# Sheet1.net
KiCad netlist of a schematic drawn in Altium Designer
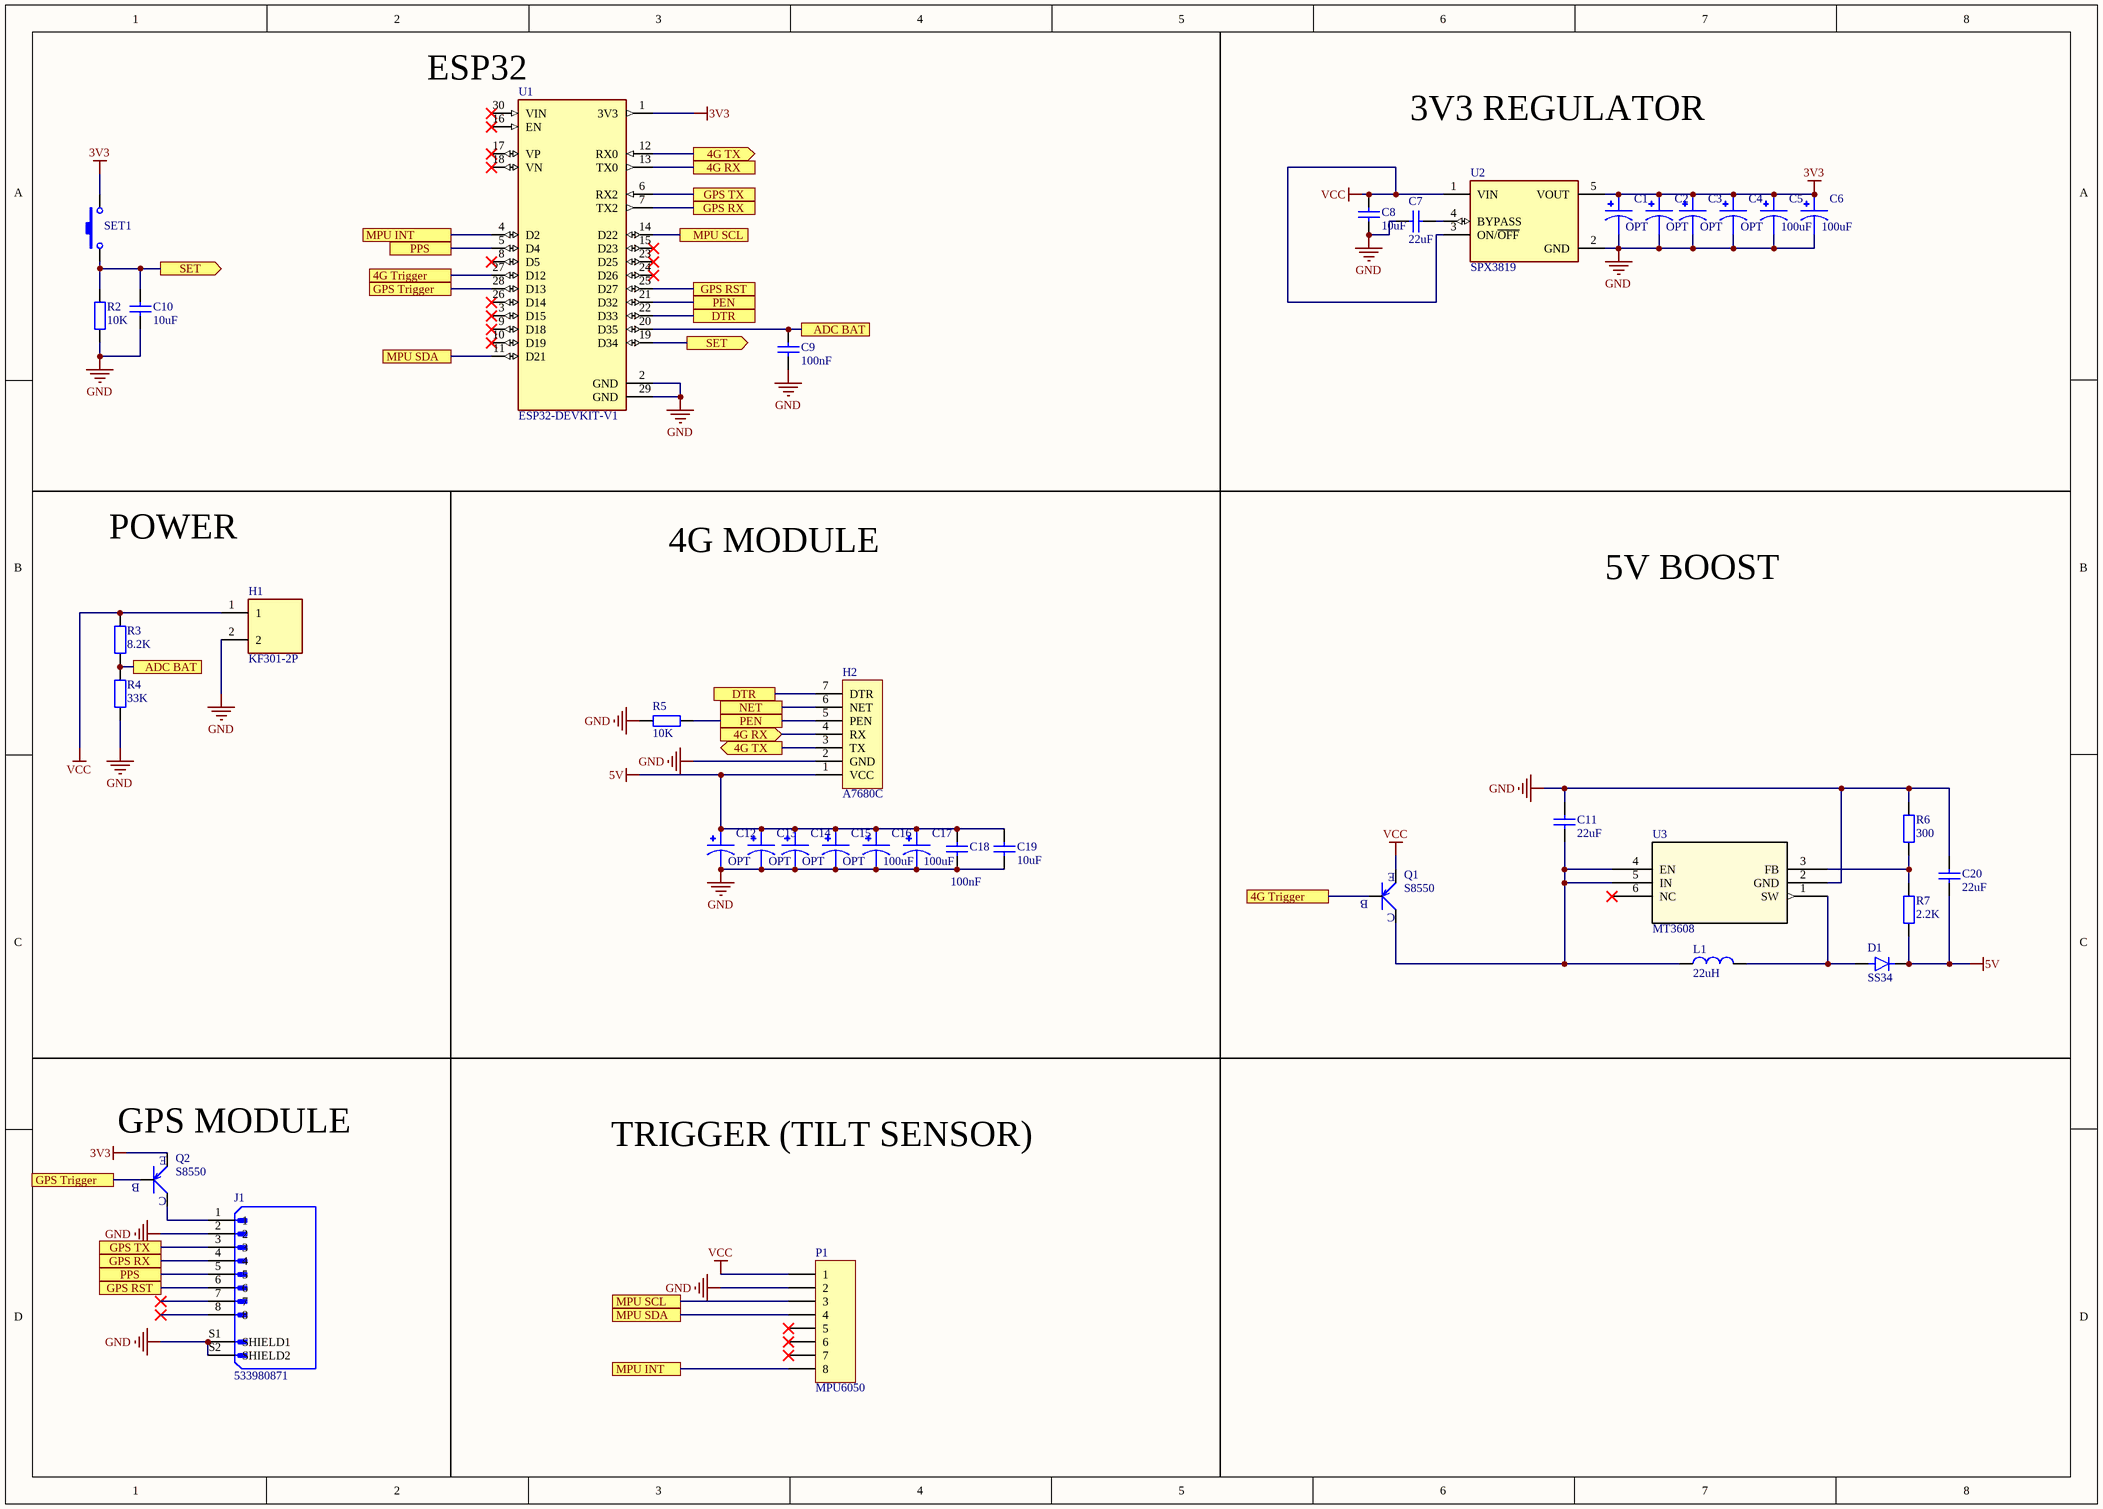
[diagram p0: Sheet1.SchDoc]

(export (version "E")
  (design (tool "Eeschema 10.0.6"))
  (components
    (comp (ref "C1")
      (value "OPT")
      (footprint "1206_Tantalum")
      (description "Molded Tantalum Capacitors")
      (libsource (lib "SAWACO") (part "Tantalum"))
    )
    (comp (ref "C2")
      (value "OPT")
      (footprint "1206_Tantalum")
      (description "Molded Tantalum Capacitors")
      (libsource (lib "SAWACO") (part "Tantalum"))
    )
    (comp (ref "C3")
      (value "OPT")
      (footprint "2312_Tantalum")
      (description "Molded Tantalum Capacitors")
      (libsource (lib "SAWACO") (part "Tantalum"))
    )
    (comp (ref "C4")
      (value "OPT")
      (footprint "2312_Tantalum")
      (description "Molded Tantalum Capacitors")
      (libsource (lib "SAWACO") (part "Tantalum"))
    )
    (comp (ref "C5")
      (value "100uF")
      (footprint "2917 _Tantalum")
      (description "Molded Tantalum Capacitors")
      (libsource (lib "SAWACO") (part "Tantalum"))
    )
    (comp (ref "C6")
      (value "100uF")
      (footprint "2917 _Tantalum")
      (description "Molded Tantalum Capacitors")
      (libsource (lib "SAWACO") (part "Tantalum"))
    )
    (comp (ref "C7")
      (value "22uF")
      (footprint "0805_Cap")
      (libsource (lib "GPS_Tracker_V1") (part "Ceramic Capacitor_1"))
    )
    (comp (ref "C8")
      (value "10uF")
      (footprint "0805_Cap")
      (libsource (lib "GPS_Tracker_V1") (part "Ceramic Capacitor_1"))
    )
    (comp (ref "C9")
      (value "100nF")
      (footprint "0805_Cap")
      (libsource (lib "GPS_Tracker") (part "Ceramic Capacitor"))
    )
    (comp (ref "C10")
      (value "10uF")
      (footprint "0805_Cap")
      (libsource (lib "GPS_Tracker") (part "Ceramic Capacitor"))
    )
    (comp (ref "C11")
      (value "22uF")
      (footprint "0805_Cap")
      (libsource (lib "SAWACO") (part "Ceramic Capacitor"))
    )
    (comp (ref "C12")
      (value "OPT")
      (footprint "1206_Tantalum")
      (description "Molded Tantalum Capacitors")
      (libsource (lib "SAWACO") (part "Tantalum"))
    )
    (comp (ref "C13")
      (value "OPT")
      (footprint "1206_Tantalum")
      (description "Molded Tantalum Capacitors")
      (libsource (lib "SAWACO") (part "Tantalum"))
    )
    (comp (ref "C14")
      (value "OPT")
      (footprint "2312_Tantalum")
      (description "Molded Tantalum Capacitors")
      (libsource (lib "SAWACO") (part "Tantalum"))
    )
    (comp (ref "C15")
      (value "OPT")
      (footprint "2312_Tantalum")
      (description "Molded Tantalum Capacitors")
      (libsource (lib "SAWACO") (part "Tantalum"))
    )
    (comp (ref "C16")
      (value "100uF")
      (footprint "2917 _Tantalum")
      (description "Molded Tantalum Capacitors")
      (libsource (lib "SAWACO") (part "Tantalum"))
    )
    (comp (ref "C17")
      (value "100uF")
      (footprint "2917 _Tantalum")
      (description "Molded Tantalum Capacitors")
      (libsource (lib "SAWACO") (part "Tantalum"))
    )
    (comp (ref "C18")
      (value "100nF")
      (footprint "0805_Cap")
      (libsource (lib "LibCOM") (part "Ceramic Capacitor"))
    )
    (comp (ref "C19")
      (value "10uF")
      (footprint "0805_Cap")
      (libsource (lib "GPS_Tracker") (part "Ceramic Capacitor"))
    )
    (comp (ref "C20")
      (value "22uF")
      (footprint "0805_Cap")
      (libsource (lib "GPS_Tracker") (part "Ceramic Capacitor"))
    )
    (comp (ref "D1")
      (value "SS34")
      (footprint "SODFL5226X100N")
      (description "3A, 40V, Schottky Rectifier")
      (fields (field (name "MP") "SS34ALH") (field (name "MF") "Taiwan Semiconductor"))
      (libsource (lib "SAWACO") (part "SS34ALH"))
    )
    (comp (ref "H1")
      (value "KF301-2P")
      (footprint "HANDSON_KF301-2P")
      (description "2 Pin Terminal Block 5mm Pitch")
      (libsource (lib "KF301-2P") (part "KF301-2P"))
    )
    (comp (ref "H2")
      (value "A7680C")
      (footprint "Module A7680C")
      (description "SIM Module A7680C; A7672S 4G")
      (libsource (lib "SAWACO") (part "Module A7680C"))
    )
    (comp (ref "J1")
      (value "533980871")
      (footprint "MOLEX_533980871")
      (libsource (lib "SAWACO") (part "533980871"))
    )
    (comp (ref "L1")
      (value "22uH")
      (footprint "INDUCTOR CDRH104")
      (fields (field (name "MP") "B82477G4472M000") (field (name "MF") "EPCOS"))
      (libsource (lib "SAWACO") (part "Inductor"))
    )
    (comp (ref "P1")
      (value "MPU6050")
      (footprint "HDR1X8")
      (description "Module MPU6050")
      (fields (field (name "PUBLISHER") "Altium Limited"))
      (libsource (lib "Miscellaneous Connectors") (part "Header 8"))
    )
    (comp (ref "Q1")
      (value "S8550")
      (footprint "SOT23")
      (description "Bipolar (BJT) Transistor PNP SOT-23")
      (fields (field (name "MF") "UMW") (field (name "MP") "S8050"))
      (libsource (lib "SAWACO") (part "S8550"))
    )
    (comp (ref "Q2")
      (value "S8550")
      (footprint "SOT23")
      (description "Bipolar (BJT) Transistor PNP SOT-23")
      (fields (field (name "MF") "UMW") (field (name "MP") "S8050"))
      (libsource (lib "SAWACO") (part "S8550"))
    )
    (comp (ref "R2") (value "10K") (footprint "0805_Res") (libsource (lib "GPS_Tracker") (part "Resistor")))
    (comp (ref "R3") (value "8.2K") (footprint "0805_Res") (libsource (lib "SAWACO") (part "Resistor")))
    (comp (ref "R4") (value "33K") (footprint "0805_Res") (libsource (lib "SAWACO") (part "Resistor")))
    (comp (ref "R5") (value "10K") (footprint "0805_Res") (libsource (lib "GPS_Tracker") (part "Resistor")))
    (comp (ref "R6") (value "300") (footprint "0805_Res") (libsource (lib "GPS_Tracker") (part "Resistor")))
    (comp (ref "R7") (value "2.2K") (footprint "0805_Res") (libsource (lib "GPS_Tracker") (part "Resistor")))
    (comp (ref "SET1")
      (value "Button 2p")
      (footprint "Button 2p 3x6x2.5")
      (description "Nut Nhan 2 Chan SMD 3x6x2.5")
      (libsource (lib "GPS_Tracker") (part "Button 2p"))
    )
    (comp (ref "U1")
      (value "ESP32-DEVKIT-V1")
      (footprint "MODULE_ESP32_DEVKIT_V1")
      (fields (field (name "MF") "Do it"))
      (libsource (lib "ESP32-DEVKIT-V1") (part "ESP32-DEVKIT-V1"))
    )
    (comp (ref "U2")
      (value "SPX3819")
      (footprint "SOT95P280X145-5N")
      (description "150-mA, 16-V, low-dropout voltage regulator with enable 5-SOT-23 -40 to 125")
      (fields (field (name "MP") "LP2985-33DBVR"))
      (libsource (lib "SAWACO_DEMO_V2") (part "LP2985-33DBVR"))
    )
    (comp (ref "U3")
      (value "MT3608")
      (footprint "TSOT23-6SOT23-6_AER")
      (description "No Description Available")
      (libsource (lib "SAWACO") (part "MT3608"))
    )
  )
  (nets
    (net (code "1") (name "/4G RX") (class "Default")
      (node (ref "H2") (pin "4") (pinfunction "RX_4") (pintype "passive"))
      (node (ref "U1") (pin "13") (pinfunction "TX0_13") (pintype "output"))
    )
    (net (code "2") (name "/4G TX") (class "Default")
      (node (ref "H2") (pin "3") (pinfunction "TX_3") (pintype "passive"))
      (node (ref "U1") (pin "12") (pinfunction "RX0_12") (pintype "input"))
    )
    (net (code "3") (name "/4G Trigger") (class "Default")
      (node (ref "Q1") (pin "1") (pinfunction "B_1") (pintype "passive"))
      (node (ref "U1") (pin "27") (pinfunction "D12_27") (pintype "bidirectional"))
    )
    (net (code "4") (name "/ADC BAT") (class "Default")
      (node (ref "C9") (pin "2") (pinfunction "2_2") (pintype "passive"))
      (node (ref "R3") (pin "1") (pinfunction "1_1") (pintype "passive"))
      (node (ref "R4") (pin "2") (pinfunction "2_2") (pintype "passive"))
      (node (ref "U1") (pin "20") (pinfunction "D35_20") (pintype "bidirectional"))
    )
    (net (code "5") (name "/DTR") (class "Default")
      (node (ref "H2") (pin "7") (pinfunction "DTR_7") (pintype "passive"))
      (node (ref "U1") (pin "22") (pinfunction "D33_22") (pintype "bidirectional"))
    )
    (net (code "6") (name "/GPS RST") (class "Default")
      (node (ref "J1") (pin "6") (pinfunction "6_6") (pintype "passive"))
      (node (ref "U1") (pin "25") (pinfunction "D27_25") (pintype "bidirectional"))
    )
    (net (code "7") (name "/GPS RX") (class "Default")
      (node (ref "J1") (pin "4") (pinfunction "4_4") (pintype "passive"))
      (node (ref "U1") (pin "7") (pinfunction "TX2_7") (pintype "output"))
    )
    (net (code "8") (name "/GPS TX") (class "Default")
      (node (ref "J1") (pin "3") (pinfunction "3_3") (pintype "passive"))
      (node (ref "U1") (pin "6") (pinfunction "RX2_6") (pintype "input"))
    )
    (net (code "9") (name "/GPS Trigger") (class "Default")
      (node (ref "Q2") (pin "1") (pinfunction "B_1") (pintype "passive"))
      (node (ref "U1") (pin "28") (pinfunction "D13_28") (pintype "bidirectional"))
    )
    (net (code "10") (name "/MPU INT") (class "Default")
      (node (ref "P1") (pin "8") (pinfunction "8_8") (pintype "passive"))
      (node (ref "U1") (pin "4") (pinfunction "D2_4") (pintype "bidirectional"))
    )
    (net (code "11") (name "/MPU SCL") (class "Default")
      (node (ref "P1") (pin "3") (pinfunction "3_3") (pintype "passive"))
      (node (ref "U1") (pin "14") (pinfunction "D22_14") (pintype "bidirectional"))
    )
    (net (code "12") (name "/MPU SDA") (class "Default")
      (node (ref "P1") (pin "4") (pinfunction "4_4") (pintype "passive"))
      (node (ref "U1") (pin "11") (pinfunction "D21_11") (pintype "bidirectional"))
    )
    (net (code "13") (name "/NET") (class "Default")
      (node (ref "H2") (pin "6") (pinfunction "NET_6") (pintype "passive"))
    )
    (net (code "14") (name "/PEN") (class "Default")
      (node (ref "H2") (pin "5") (pinfunction "PEN_5") (pintype "passive"))
      (node (ref "R5") (pin "1") (pinfunction "1_1") (pintype "passive"))
      (node (ref "U1") (pin "21") (pinfunction "D32_21") (pintype "bidirectional"))
    )
    (net (code "15") (name "/PPS") (class "Default")
      (node (ref "J1") (pin "5") (pinfunction "5_5") (pintype "passive"))
      (node (ref "U1") (pin "5") (pinfunction "D4_5") (pintype "bidirectional"))
    )
    (net (code "16") (name "/SET") (class "Default")
      (node (ref "C10") (pin "1") (pinfunction "1_1") (pintype "passive"))
      (node (ref "R2") (pin "2") (pinfunction "2_2") (pintype "passive"))
      (node (ref "SET1") (pin "1") (pinfunction "1_1") (pintype "passive"))
      (node (ref "U1") (pin "19") (pinfunction "D34_19") (pintype "bidirectional"))
    )
    (net (code "17") (name "3V3") (class "Default")
      (node (ref "C1") (pin "1") (pinfunction "1_1") (pintype "passive"))
      (node (ref "C2") (pin "1") (pinfunction "1_1") (pintype "passive"))
      (node (ref "C3") (pin "1") (pinfunction "1_1") (pintype "passive"))
      (node (ref "C4") (pin "1") (pinfunction "1_1") (pintype "passive"))
      (node (ref "C5") (pin "1") (pinfunction "1_1") (pintype "passive"))
      (node (ref "C6") (pin "1") (pinfunction "1_1") (pintype "passive"))
      (node (ref "Q2") (pin "2") (pinfunction "E_2") (pintype "passive"))
      (node (ref "SET1") (pin "2") (pinfunction "2_2") (pintype "passive"))
      (node (ref "U1") (pin "1") (pinfunction "3V3_1") (pintype "output"))
      (node (ref "U2") (pin "5") (pinfunction "VOUT_5") (pintype "passive"))
    )
    (net (code "18") (name "5V") (class "Default")
      (node (ref "C12") (pin "1") (pinfunction "1_1") (pintype "passive"))
      (node (ref "C13") (pin "1") (pinfunction "1_1") (pintype "passive"))
      (node (ref "C14") (pin "1") (pinfunction "1_1") (pintype "passive"))
      (node (ref "C15") (pin "1") (pinfunction "1_1") (pintype "passive"))
      (node (ref "C16") (pin "1") (pinfunction "1_1") (pintype "passive"))
      (node (ref "C17") (pin "1") (pinfunction "1_1") (pintype "passive"))
      (node (ref "C18") (pin "1") (pinfunction "1_1") (pintype "passive"))
      (node (ref "C19") (pin "2") (pinfunction "2_2") (pintype "passive"))
      (node (ref "C20") (pin "1") (pinfunction "1_1") (pintype "passive"))
      (node (ref "D1") (pin "1") (pinfunction "K_1") (pintype "passive"))
      (node (ref "H2") (pin "1") (pinfunction "VCC_1") (pintype "passive"))
      (node (ref "R7") (pin "1") (pinfunction "1_1") (pintype "passive"))
    )
    (net (code "19") (name "GND") (class "Default")
      (node (ref "C1") (pin "2") (pinfunction "2_2") (pintype "passive"))
      (node (ref "C10") (pin "2") (pinfunction "2_2") (pintype "passive"))
      (node (ref "C11") (pin "1") (pinfunction "1_1") (pintype "passive"))
      (node (ref "C12") (pin "2") (pinfunction "2_2") (pintype "passive"))
      (node (ref "C13") (pin "2") (pinfunction "2_2") (pintype "passive"))
      (node (ref "C14") (pin "2") (pinfunction "2_2") (pintype "passive"))
      (node (ref "C15") (pin "2") (pinfunction "2_2") (pintype "passive"))
      (node (ref "C16") (pin "2") (pinfunction "2_2") (pintype "passive"))
      (node (ref "C17") (pin "2") (pinfunction "2_2") (pintype "passive"))
      (node (ref "C18") (pin "2") (pinfunction "2_2") (pintype "passive"))
      (node (ref "C19") (pin "1") (pinfunction "1_1") (pintype "passive"))
      (node (ref "C2") (pin "2") (pinfunction "2_2") (pintype "passive"))
      (node (ref "C20") (pin "2") (pinfunction "2_2") (pintype "passive"))
      (node (ref "C3") (pin "2") (pinfunction "2_2") (pintype "passive"))
      (node (ref "C4") (pin "2") (pinfunction "2_2") (pintype "passive"))
      (node (ref "C5") (pin "2") (pinfunction "2_2") (pintype "passive"))
      (node (ref "C6") (pin "2") (pinfunction "2_2") (pintype "passive"))
      (node (ref "C7") (pin "2") (pinfunction "2_2") (pintype "passive"))
      (node (ref "C8") (pin "1") (pinfunction "1_1") (pintype "passive"))
      (node (ref "C9") (pin "1") (pinfunction "1_1") (pintype "passive"))
      (node (ref "H1") (pin "2") (pinfunction "2_2") (pintype "passive"))
      (node (ref "H2") (pin "2") (pinfunction "GND_2") (pintype "passive"))
      (node (ref "J1") (pin "2") (pinfunction "2_2") (pintype "passive"))
      (node (ref "J1") (pin "S1") (pinfunction "SHIELD1_S1") (pintype "passive"))
      (node (ref "J1") (pin "S2") (pinfunction "SHIELD2_S2") (pintype "passive"))
      (node (ref "P1") (pin "2") (pinfunction "2_2") (pintype "passive"))
      (node (ref "R2") (pin "1") (pinfunction "1_1") (pintype "passive"))
      (node (ref "R4") (pin "1") (pinfunction "1_1") (pintype "passive"))
      (node (ref "R5") (pin "2") (pinfunction "2_2") (pintype "passive"))
      (node (ref "R6") (pin "2") (pinfunction "2_2") (pintype "passive"))
      (node (ref "U1") (pin "2") (pinfunction "GND_2") (pintype "power_in"))
      (node (ref "U1") (pin "29") (pinfunction "GND_29") (pintype "power_in"))
      (node (ref "U2") (pin "2") (pinfunction "GND_2") (pintype "power_in"))
      (node (ref "U3") (pin "2") (pinfunction "GND_2") (pintype "power_in"))
    )
    (net (code "20") (name "Net-(D1-A)") (class "Default")
      (node (ref "D1") (pin "2") (pinfunction "A_2") (pintype "passive"))
      (node (ref "L1") (pin "2") (pinfunction "2_2") (pintype "passive"))
      (node (ref "U3") (pin "1") (pinfunction "SW_1") (pintype "output"))
    )
    (net (code "21") (name "Net-(Q1-C)") (class "Default")
      (node (ref "C11") (pin "2") (pinfunction "2_2") (pintype "passive"))
      (node (ref "L1") (pin "1") (pinfunction "1_1") (pintype "passive"))
      (node (ref "Q1") (pin "3") (pinfunction "C_3") (pintype "passive"))
      (node (ref "U3") (pin "4") (pinfunction "EN_4") (pintype "passive"))
      (node (ref "U3") (pin "5") (pinfunction "IN_5") (pintype "power_in"))
    )
    (net (code "22") (name "Net-(Q2-C)") (class "Default")
      (node (ref "J1") (pin "1") (pinfunction "1_1") (pintype "passive"))
      (node (ref "Q2") (pin "3") (pinfunction "C_3") (pintype "passive"))
    )
    (net (code "23") (name "Net-(U2-BYPASS)") (class "Default")
      (node (ref "C7") (pin "1") (pinfunction "1_1") (pintype "passive"))
      (node (ref "U2") (pin "4") (pinfunction "BYPASS_4") (pintype "bidirectional"))
    )
    (net (code "24") (name "Net-(U3-FB)") (class "Default")
      (node (ref "R6") (pin "1") (pinfunction "1_1") (pintype "passive"))
      (node (ref "R7") (pin "2") (pinfunction "2_2") (pintype "passive"))
      (node (ref "U3") (pin "3") (pinfunction "FB_3") (pintype "passive"))
    )
    (net (code "25") (name "VCC") (class "Default")
      (node (ref "C8") (pin "2") (pinfunction "2_2") (pintype "passive"))
      (node (ref "H1") (pin "1") (pinfunction "1_1") (pintype "passive"))
      (node (ref "P1") (pin "1") (pinfunction "1_1") (pintype "passive"))
      (node (ref "Q1") (pin "2") (pinfunction "E_2") (pintype "passive"))
      (node (ref "R3") (pin "2") (pinfunction "2_2") (pintype "passive"))
      (node (ref "U2") (pin "1") (pinfunction "VIN_1") (pintype "passive"))
      (node (ref "U2") (pin "3") (pinfunction "ON/~{OFF}_3") (pintype "passive"))
    )
    (net (code "26") (name "unconnected-(J1-Pad7)") (class "Default")
      (node (ref "J1") (pin "7") (pinfunction "7_7") (pintype "passive+no_connect"))
    )
    (net (code "27") (name "unconnected-(J1-Pad8)") (class "Default")
      (node (ref "J1") (pin "8") (pinfunction "8_8") (pintype "passive+no_connect"))
    )
    (net (code "28") (name "unconnected-(P1-Pad5)") (class "Default")
      (node (ref "P1") (pin "5") (pinfunction "5_5") (pintype "passive+no_connect"))
    )
    (net (code "29") (name "unconnected-(P1-Pad6)") (class "Default")
      (node (ref "P1") (pin "6") (pinfunction "6_6") (pintype "passive+no_connect"))
    )
    (net (code "30") (name "unconnected-(P1-Pad7)") (class "Default")
      (node (ref "P1") (pin "7") (pinfunction "7_7") (pintype "passive+no_connect"))
    )
    (net (code "31") (name "unconnected-(U1-D5-Pad8)") (class "Default")
      (node (ref "U1") (pin "8") (pinfunction "D5_8") (pintype "bidirectional+no_connect"))
    )
    (net (code "32") (name "unconnected-(U1-D14-Pad26)") (class "Default")
      (node (ref "U1") (pin "26") (pinfunction "D14_26") (pintype "bidirectional+no_connect"))
    )
    (net (code "33") (name "unconnected-(U1-D15-Pad3)") (class "Default")
      (node (ref "U1") (pin "3") (pinfunction "D15_3") (pintype "bidirectional+no_connect"))
    )
    (net (code "34") (name "unconnected-(U1-D18-Pad9)") (class "Default")
      (node (ref "U1") (pin "9") (pinfunction "D18_9") (pintype "bidirectional+no_connect"))
    )
    (net (code "35") (name "unconnected-(U1-D19-Pad10)") (class "Default")
      (node (ref "U1") (pin "10") (pinfunction "D19_10") (pintype "bidirectional+no_connect"))
    )
    (net (code "36") (name "unconnected-(U1-D23-Pad15)") (class "Default")
      (node (ref "U1") (pin "15") (pinfunction "D23_15") (pintype "bidirectional+no_connect"))
    )
    (net (code "37") (name "unconnected-(U1-D25-Pad23)") (class "Default")
      (node (ref "U1") (pin "23") (pinfunction "D25_23") (pintype "bidirectional+no_connect"))
    )
    (net (code "38") (name "unconnected-(U1-D26-Pad24)") (class "Default")
      (node (ref "U1") (pin "24") (pinfunction "D26_24") (pintype "bidirectional+no_connect"))
    )
    (net (code "39") (name "unconnected-(U1-EN-Pad16)") (class "Default")
      (node (ref "U1") (pin "16") (pinfunction "EN_16") (pintype "input+no_connect"))
    )
    (net (code "40") (name "unconnected-(U1-VIN-Pad30)") (class "Default")
      (node (ref "U1") (pin "30") (pinfunction "VIN_30") (pintype "input+no_connect"))
    )
    (net (code "41") (name "unconnected-(U1-VN-Pad18)") (class "Default")
      (node (ref "U1") (pin "18") (pinfunction "VN_18") (pintype "bidirectional+no_connect"))
    )
    (net (code "42") (name "unconnected-(U1-VP-Pad17)") (class "Default")
      (node (ref "U1") (pin "17") (pinfunction "VP_17") (pintype "bidirectional+no_connect"))
    )
    (net (code "43") (name "unconnected-(U3-NC-Pad6)") (class "Default")
      (node (ref "U3") (pin "6") (pinfunction "NC_6") (pintype "passive+no_connect"))
    )
  )
)
